# W975.net
KiCad netlist of a schematic drawn in EAGLE
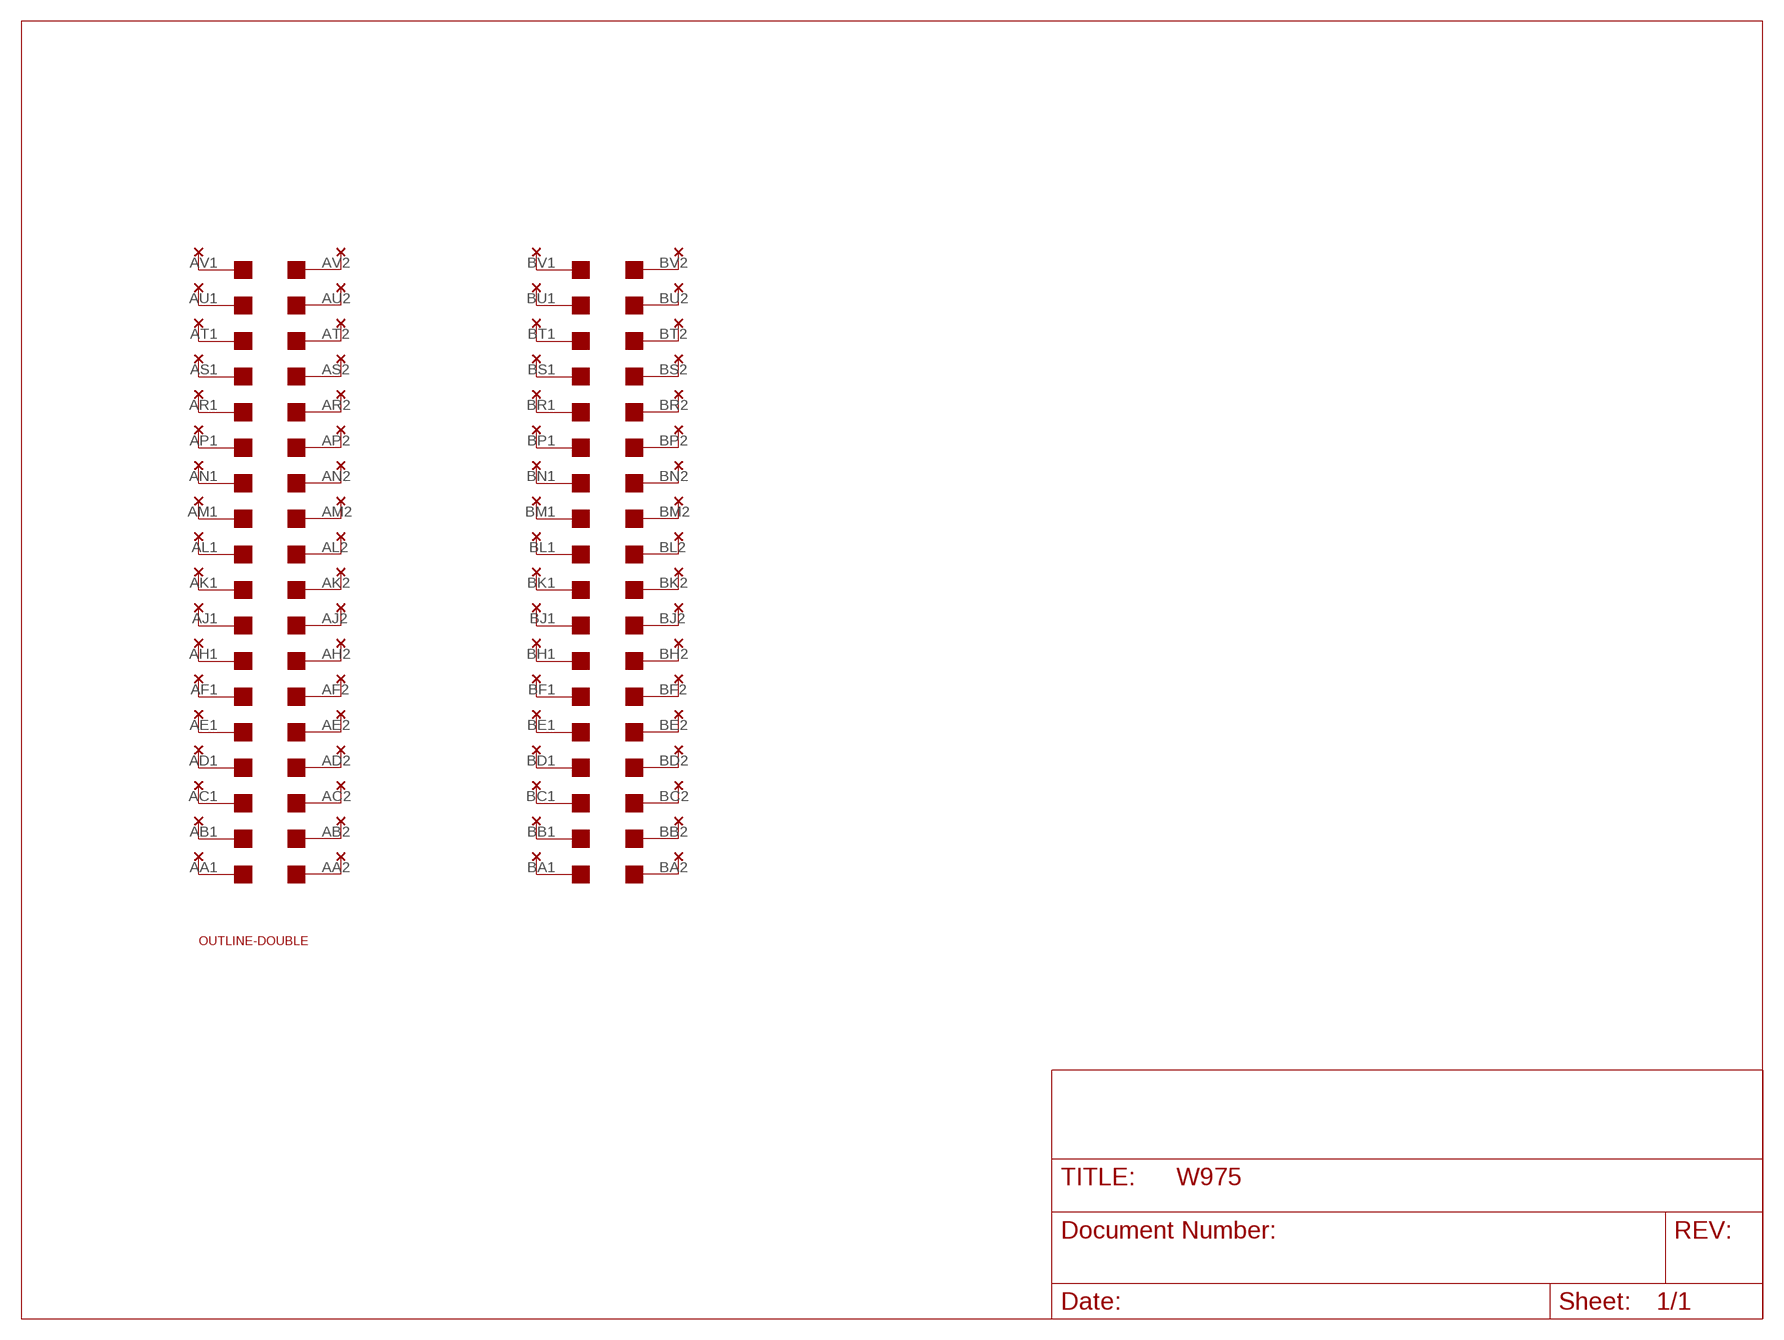
[diagram p0: schematic, sheet 1]

(export (version "E")
  (design (tool "Eeschema 10.0.6"))
  (components
    (comp (ref "A")
      (value "A")
      (footprint "eagle-import:THRU-HOLE2")
      (libsource (lib "eagle-import") (part "THRU-HOLE2W"))
    )
    (comp (ref "B")
      (value "B")
      (footprint "eagle-import:THRU-HOLE2")
      (libsource (lib "eagle-import") (part "THRU-HOLE2W"))
    )
    (comp (ref "U$1")
      (value "OUTLINE-DOUBLE")
      (footprint "eagle-import:DOUBLE")
      (libsource (lib "eagle-import") (part "OUTLINE-DOUBLE"))
    )
    (comp (ref "U$2")
      (value "DOUBLE")
      (footprint "eagle-import:EDGE-CON4")
      (libsource (lib "eagle-import") (part "DOUBLE"))
    )
  )
  (nets
    (net (code "1") (name "Net-(AA-P$1)") (class "Default")
      (node (ref "A") (pin "A1") (pinfunction "P$1_A1") (pintype "passive"))
      (node (ref "U$2") (pin "AA1") (pinfunction "1_AA1") (pintype "bidirectional"))
    )
    (net (code "2") (name "Net-(AAA-P$1)") (class "Default")
      (node (ref "A") (pin "R1") (pinfunction "P$1_R1") (pintype "passive"))
      (node (ref "U$2") (pin "AR1") (pinfunction "1_AR1") (pintype "bidirectional"))
    )
    (net (code "3") (name "Net-(AAB-P$1)") (class "Default")
      (node (ref "A") (pin "R2") (pinfunction "P$1_R2") (pintype "passive"))
      (node (ref "U$2") (pin "AR2") (pinfunction "1_AR2") (pintype "bidirectional"))
    )
    (net (code "4") (name "Net-(AAC-P$1)") (class "Default")
      (node (ref "A") (pin "S1") (pinfunction "P$1_S1") (pintype "passive"))
      (node (ref "U$2") (pin "AS1") (pinfunction "1_AS1") (pintype "bidirectional"))
    )
    (net (code "5") (name "Net-(AAD-P$1)") (class "Default")
      (node (ref "A") (pin "S2") (pinfunction "P$1_S2") (pintype "passive"))
      (node (ref "U$2") (pin "AS2") (pinfunction "1_AS2") (pintype "bidirectional"))
    )
    (net (code "6") (name "Net-(AAE-P$1)") (class "Default")
      (node (ref "A") (pin "T1") (pinfunction "P$1_T1") (pintype "passive"))
      (node (ref "U$2") (pin "AT1") (pinfunction "1_AT1") (pintype "bidirectional"))
    )
    (net (code "7") (name "Net-(AAF-P$1)") (class "Default")
      (node (ref "A") (pin "T2") (pinfunction "P$1_T2") (pintype "passive"))
      (node (ref "U$2") (pin "AT2") (pinfunction "1_AT2") (pintype "bidirectional"))
    )
    (net (code "8") (name "Net-(AAG-P$1)") (class "Default")
      (node (ref "A") (pin "U1") (pinfunction "P$1_U1") (pintype "passive"))
      (node (ref "U$2") (pin "AU1") (pinfunction "1_AU1") (pintype "bidirectional"))
    )
    (net (code "9") (name "Net-(AAH-P$1)") (class "Default")
      (node (ref "A") (pin "U2") (pinfunction "P$1_U2") (pintype "passive"))
      (node (ref "U$2") (pin "AU2") (pinfunction "1_AU2") (pintype "bidirectional"))
    )
    (net (code "10") (name "Net-(AAI-P$1)") (class "Default")
      (node (ref "A") (pin "V1") (pinfunction "P$1_V1") (pintype "passive"))
      (node (ref "U$2") (pin "AV1") (pinfunction "1_AV1") (pintype "bidirectional"))
    )
    (net (code "11") (name "Net-(AAJ-P$1)") (class "Default")
      (node (ref "A") (pin "V2") (pinfunction "P$1_V2") (pintype "passive"))
      (node (ref "U$2") (pin "AV2") (pinfunction "1_AV2") (pintype "bidirectional"))
    )
    (net (code "12") (name "Net-(AB-P$1)") (class "Default")
      (node (ref "A") (pin "A2") (pinfunction "P$1_A2") (pintype "passive"))
      (node (ref "U$2") (pin "AA2") (pinfunction "1_AA2") (pintype "bidirectional"))
    )
    (net (code "13") (name "Net-(AC-P$1)") (class "Default")
      (node (ref "A") (pin "B1") (pinfunction "P$1_B1") (pintype "passive"))
      (node (ref "U$2") (pin "AB1") (pinfunction "1_AB1") (pintype "bidirectional"))
    )
    (net (code "14") (name "Net-(AD-P$1)") (class "Default")
      (node (ref "A") (pin "B2") (pinfunction "P$1_B2") (pintype "passive"))
      (node (ref "U$2") (pin "AB2") (pinfunction "1_AB2") (pintype "bidirectional"))
    )
    (net (code "15") (name "Net-(AE-P$1)") (class "Default")
      (node (ref "A") (pin "C1") (pinfunction "P$1_C1") (pintype "passive"))
      (node (ref "U$2") (pin "AC1") (pinfunction "1_AC1") (pintype "bidirectional"))
    )
    (net (code "16") (name "Net-(AF-P$1)") (class "Default")
      (node (ref "A") (pin "C2") (pinfunction "P$1_C2") (pintype "passive"))
      (node (ref "U$2") (pin "AC2") (pinfunction "1_AC2") (pintype "bidirectional"))
    )
    (net (code "17") (name "Net-(AG-P$1)") (class "Default")
      (node (ref "A") (pin "D1") (pinfunction "P$1_D1") (pintype "passive"))
      (node (ref "U$2") (pin "AD1") (pinfunction "1_AD1") (pintype "bidirectional"))
    )
    (net (code "18") (name "Net-(AH-P$1)") (class "Default")
      (node (ref "A") (pin "D2") (pinfunction "P$1_D2") (pintype "passive"))
      (node (ref "U$2") (pin "AD2") (pinfunction "1_AD2") (pintype "bidirectional"))
    )
    (net (code "19") (name "Net-(AI-P$1)") (class "Default")
      (node (ref "A") (pin "E1") (pinfunction "P$1_E1") (pintype "passive"))
      (node (ref "U$2") (pin "AE1") (pinfunction "1_AE1") (pintype "bidirectional"))
    )
    (net (code "20") (name "Net-(AJ-P$1)") (class "Default")
      (node (ref "A") (pin "E2") (pinfunction "P$1_E2") (pintype "passive"))
      (node (ref "U$2") (pin "AE2") (pinfunction "1_AE2") (pintype "bidirectional"))
    )
    (net (code "21") (name "Net-(AK-P$1)") (class "Default")
      (node (ref "A") (pin "F1") (pinfunction "P$1_F1") (pintype "passive"))
      (node (ref "U$2") (pin "AF1") (pinfunction "1_AF1") (pintype "bidirectional"))
    )
    (net (code "22") (name "Net-(AL-P$1)") (class "Default")
      (node (ref "A") (pin "F2") (pinfunction "P$1_F2") (pintype "passive"))
      (node (ref "U$2") (pin "AF2") (pinfunction "1_AF2") (pintype "bidirectional"))
    )
    (net (code "23") (name "Net-(AM-P$1)") (class "Default")
      (node (ref "A") (pin "H1") (pinfunction "P$1_H1") (pintype "passive"))
      (node (ref "U$2") (pin "AH1") (pinfunction "1_AH1") (pintype "bidirectional"))
    )
    (net (code "24") (name "Net-(AN-P$1)") (class "Default")
      (node (ref "A") (pin "H2") (pinfunction "P$1_H2") (pintype "passive"))
      (node (ref "U$2") (pin "AH2") (pinfunction "1_AH2") (pintype "bidirectional"))
    )
    (net (code "25") (name "Net-(AO-P$1)") (class "Default")
      (node (ref "A") (pin "J1") (pinfunction "P$1_J1") (pintype "passive"))
      (node (ref "U$2") (pin "AJ1") (pinfunction "1_AJ1") (pintype "bidirectional"))
    )
    (net (code "26") (name "Net-(AP-P$1)") (class "Default")
      (node (ref "A") (pin "J2") (pinfunction "P$1_J2") (pintype "passive"))
      (node (ref "U$2") (pin "AJ2") (pinfunction "1_AJ2") (pintype "bidirectional"))
    )
    (net (code "27") (name "Net-(AQ-P$1)") (class "Default")
      (node (ref "A") (pin "K1") (pinfunction "P$1_K1") (pintype "passive"))
      (node (ref "U$2") (pin "AK1") (pinfunction "1_AK1") (pintype "bidirectional"))
    )
    (net (code "28") (name "Net-(AR-P$1)") (class "Default")
      (node (ref "A") (pin "K2") (pinfunction "P$1_K2") (pintype "passive"))
      (node (ref "U$2") (pin "AK2") (pinfunction "1_AK2") (pintype "bidirectional"))
    )
    (net (code "29") (name "Net-(AS-P$1)") (class "Default")
      (node (ref "A") (pin "L1") (pinfunction "P$1_L1") (pintype "passive"))
      (node (ref "U$2") (pin "AL1") (pinfunction "1_AL1") (pintype "bidirectional"))
    )
    (net (code "30") (name "Net-(AT-P$1)") (class "Default")
      (node (ref "A") (pin "L2") (pinfunction "P$1_L2") (pintype "passive"))
      (node (ref "U$2") (pin "AL2") (pinfunction "1_AL2") (pintype "bidirectional"))
    )
    (net (code "31") (name "Net-(AU-P$1)") (class "Default")
      (node (ref "A") (pin "M1") (pinfunction "P$1_M1") (pintype "passive"))
      (node (ref "U$2") (pin "AM1") (pinfunction "1_AM1") (pintype "bidirectional"))
    )
    (net (code "32") (name "Net-(AV-P$1)") (class "Default")
      (node (ref "A") (pin "M2") (pinfunction "P$1_M2") (pintype "passive"))
      (node (ref "U$2") (pin "AM2") (pinfunction "1_AM2") (pintype "bidirectional"))
    )
    (net (code "33") (name "Net-(AW-P$1)") (class "Default")
      (node (ref "A") (pin "N1") (pinfunction "P$1_N1") (pintype "passive"))
      (node (ref "U$2") (pin "AN1") (pinfunction "1_AN1") (pintype "bidirectional"))
    )
    (net (code "34") (name "Net-(AX-P$1)") (class "Default")
      (node (ref "A") (pin "N2") (pinfunction "P$1_N2") (pintype "passive"))
      (node (ref "U$2") (pin "AN2") (pinfunction "1_AN2") (pintype "bidirectional"))
    )
    (net (code "35") (name "Net-(AY-P$1)") (class "Default")
      (node (ref "A") (pin "P1") (pinfunction "P$1_P1") (pintype "passive"))
      (node (ref "U$2") (pin "AP1") (pinfunction "1_AP1") (pintype "bidirectional"))
    )
    (net (code "36") (name "Net-(AZ-P$1)") (class "Default")
      (node (ref "A") (pin "P2") (pinfunction "P$1_P2") (pintype "passive"))
      (node (ref "U$2") (pin "AP2") (pinfunction "1_AP2") (pintype "bidirectional"))
    )
    (net (code "37") (name "Net-(BA-P$1)") (class "Default")
      (node (ref "B") (pin "A1") (pinfunction "P$1_A1") (pintype "passive"))
      (node (ref "U$2") (pin "BA1") (pinfunction "1_BA1") (pintype "bidirectional"))
    )
    (net (code "38") (name "Net-(BAA-P$1)") (class "Default")
      (node (ref "B") (pin "R1") (pinfunction "P$1_R1") (pintype "passive"))
      (node (ref "U$2") (pin "BR1") (pinfunction "1_BR1") (pintype "bidirectional"))
    )
    (net (code "39") (name "Net-(BAB-P$1)") (class "Default")
      (node (ref "B") (pin "R2") (pinfunction "P$1_R2") (pintype "passive"))
      (node (ref "U$2") (pin "BR2") (pinfunction "1_BR2") (pintype "bidirectional"))
    )
    (net (code "40") (name "Net-(BAC-P$1)") (class "Default")
      (node (ref "B") (pin "S1") (pinfunction "P$1_S1") (pintype "passive"))
      (node (ref "U$2") (pin "BS1") (pinfunction "1_BS1") (pintype "bidirectional"))
    )
    (net (code "41") (name "Net-(BAD-P$1)") (class "Default")
      (node (ref "B") (pin "S2") (pinfunction "P$1_S2") (pintype "passive"))
      (node (ref "U$2") (pin "BS2") (pinfunction "1_BS2") (pintype "bidirectional"))
    )
    (net (code "42") (name "Net-(BAE-P$1)") (class "Default")
      (node (ref "B") (pin "T1") (pinfunction "P$1_T1") (pintype "passive"))
      (node (ref "U$2") (pin "BT1") (pinfunction "1_BT1") (pintype "bidirectional"))
    )
    (net (code "43") (name "Net-(BAF-P$1)") (class "Default")
      (node (ref "B") (pin "T2") (pinfunction "P$1_T2") (pintype "passive"))
      (node (ref "U$2") (pin "BT2") (pinfunction "1_BT2") (pintype "bidirectional"))
    )
    (net (code "44") (name "Net-(BAG-P$1)") (class "Default")
      (node (ref "B") (pin "U1") (pinfunction "P$1_U1") (pintype "passive"))
      (node (ref "U$2") (pin "BU1") (pinfunction "1_BU1") (pintype "bidirectional"))
    )
    (net (code "45") (name "Net-(BAH-P$1)") (class "Default")
      (node (ref "B") (pin "U2") (pinfunction "P$1_U2") (pintype "passive"))
      (node (ref "U$2") (pin "BU2") (pinfunction "1_BU2") (pintype "bidirectional"))
    )
    (net (code "46") (name "Net-(BAI-P$1)") (class "Default")
      (node (ref "B") (pin "V1") (pinfunction "P$1_V1") (pintype "passive"))
      (node (ref "U$2") (pin "BV1") (pinfunction "1_BV1") (pintype "bidirectional"))
    )
    (net (code "47") (name "Net-(BAJ-P$1)") (class "Default")
      (node (ref "B") (pin "V2") (pinfunction "P$1_V2") (pintype "passive"))
      (node (ref "U$2") (pin "BV2") (pinfunction "1_BV2") (pintype "bidirectional"))
    )
    (net (code "48") (name "Net-(BB-P$1)") (class "Default")
      (node (ref "B") (pin "A2") (pinfunction "P$1_A2") (pintype "passive"))
      (node (ref "U$2") (pin "BA2") (pinfunction "1_BA2") (pintype "bidirectional"))
    )
    (net (code "49") (name "Net-(BC-P$1)") (class "Default")
      (node (ref "B") (pin "B1") (pinfunction "P$1_B1") (pintype "passive"))
      (node (ref "U$2") (pin "BB1") (pinfunction "1_BB1") (pintype "bidirectional"))
    )
    (net (code "50") (name "Net-(BD-P$1)") (class "Default")
      (node (ref "B") (pin "B2") (pinfunction "P$1_B2") (pintype "passive"))
      (node (ref "U$2") (pin "BB2") (pinfunction "1_BB2") (pintype "bidirectional"))
    )
    (net (code "51") (name "Net-(BE-P$1)") (class "Default")
      (node (ref "B") (pin "C1") (pinfunction "P$1_C1") (pintype "passive"))
      (node (ref "U$2") (pin "BC1") (pinfunction "1_BC1") (pintype "bidirectional"))
    )
    (net (code "52") (name "Net-(BF-P$1)") (class "Default")
      (node (ref "B") (pin "C2") (pinfunction "P$1_C2") (pintype "passive"))
      (node (ref "U$2") (pin "BC2") (pinfunction "1_BC2") (pintype "bidirectional"))
    )
    (net (code "53") (name "Net-(BG-P$1)") (class "Default")
      (node (ref "B") (pin "D1") (pinfunction "P$1_D1") (pintype "passive"))
      (node (ref "U$2") (pin "BD1") (pinfunction "1_BD1") (pintype "bidirectional"))
    )
    (net (code "54") (name "Net-(BH-P$1)") (class "Default")
      (node (ref "B") (pin "D2") (pinfunction "P$1_D2") (pintype "passive"))
      (node (ref "U$2") (pin "BD2") (pinfunction "1_BD2") (pintype "bidirectional"))
    )
    (net (code "55") (name "Net-(BI-P$1)") (class "Default")
      (node (ref "B") (pin "E1") (pinfunction "P$1_E1") (pintype "passive"))
      (node (ref "U$2") (pin "BE1") (pinfunction "1_BE1") (pintype "bidirectional"))
    )
    (net (code "56") (name "Net-(BJ-P$1)") (class "Default")
      (node (ref "B") (pin "E2") (pinfunction "P$1_E2") (pintype "passive"))
      (node (ref "U$2") (pin "BE2") (pinfunction "1_BE2") (pintype "bidirectional"))
    )
    (net (code "57") (name "Net-(BK-P$1)") (class "Default")
      (node (ref "B") (pin "F1") (pinfunction "P$1_F1") (pintype "passive"))
      (node (ref "U$2") (pin "BF1") (pinfunction "1_BF1") (pintype "bidirectional"))
    )
    (net (code "58") (name "Net-(BL-P$1)") (class "Default")
      (node (ref "B") (pin "F2") (pinfunction "P$1_F2") (pintype "passive"))
      (node (ref "U$2") (pin "BF2") (pinfunction "1_BF2") (pintype "bidirectional"))
    )
    (net (code "59") (name "Net-(BM-P$1)") (class "Default")
      (node (ref "B") (pin "H1") (pinfunction "P$1_H1") (pintype "passive"))
      (node (ref "U$2") (pin "BH1") (pinfunction "1_BH1") (pintype "bidirectional"))
    )
    (net (code "60") (name "Net-(BN-P$1)") (class "Default")
      (node (ref "B") (pin "H2") (pinfunction "P$1_H2") (pintype "passive"))
      (node (ref "U$2") (pin "BH2") (pinfunction "1_BH2") (pintype "bidirectional"))
    )
    (net (code "61") (name "Net-(BO-P$1)") (class "Default")
      (node (ref "B") (pin "J1") (pinfunction "P$1_J1") (pintype "passive"))
      (node (ref "U$2") (pin "BJ1") (pinfunction "1_BJ1") (pintype "bidirectional"))
    )
    (net (code "62") (name "Net-(BP-P$1)") (class "Default")
      (node (ref "B") (pin "J2") (pinfunction "P$1_J2") (pintype "passive"))
      (node (ref "U$2") (pin "BJ2") (pinfunction "1_BJ2") (pintype "bidirectional"))
    )
    (net (code "63") (name "Net-(BQ-P$1)") (class "Default")
      (node (ref "B") (pin "K1") (pinfunction "P$1_K1") (pintype "passive"))
      (node (ref "U$2") (pin "BK1") (pinfunction "1_BK1") (pintype "bidirectional"))
    )
    (net (code "64") (name "Net-(BR-P$1)") (class "Default")
      (node (ref "B") (pin "K2") (pinfunction "P$1_K2") (pintype "passive"))
      (node (ref "U$2") (pin "BK2") (pinfunction "1_BK2") (pintype "bidirectional"))
    )
    (net (code "65") (name "Net-(BS-P$1)") (class "Default")
      (node (ref "B") (pin "L1") (pinfunction "P$1_L1") (pintype "passive"))
      (node (ref "U$2") (pin "BL1") (pinfunction "1_BL1") (pintype "bidirectional"))
    )
    (net (code "66") (name "Net-(BT-P$1)") (class "Default")
      (node (ref "B") (pin "L2") (pinfunction "P$1_L2") (pintype "passive"))
      (node (ref "U$2") (pin "BL2") (pinfunction "1_BL2") (pintype "bidirectional"))
    )
    (net (code "67") (name "Net-(BU-P$1)") (class "Default")
      (node (ref "B") (pin "M1") (pinfunction "P$1_M1") (pintype "passive"))
      (node (ref "U$2") (pin "BM1") (pinfunction "1_BM1") (pintype "bidirectional"))
    )
    (net (code "68") (name "Net-(BV-P$1)") (class "Default")
      (node (ref "B") (pin "M2") (pinfunction "P$1_M2") (pintype "passive"))
      (node (ref "U$2") (pin "BM2") (pinfunction "1_BM2") (pintype "bidirectional"))
    )
    (net (code "69") (name "Net-(BW-P$1)") (class "Default")
      (node (ref "B") (pin "N1") (pinfunction "P$1_N1") (pintype "passive"))
      (node (ref "U$2") (pin "BN1") (pinfunction "1_BN1") (pintype "bidirectional"))
    )
    (net (code "70") (name "Net-(BX-P$1)") (class "Default")
      (node (ref "B") (pin "N2") (pinfunction "P$1_N2") (pintype "passive"))
      (node (ref "U$2") (pin "BN2") (pinfunction "1_BN2") (pintype "bidirectional"))
    )
    (net (code "71") (name "Net-(BY-P$1)") (class "Default")
      (node (ref "B") (pin "P1") (pinfunction "P$1_P1") (pintype "passive"))
      (node (ref "U$2") (pin "BP1") (pinfunction "1_BP1") (pintype "bidirectional"))
    )
    (net (code "72") (name "Net-(BZ-P$1)") (class "Default")
      (node (ref "B") (pin "P2") (pinfunction "P$1_P2") (pintype "passive"))
      (node (ref "U$2") (pin "BP2") (pinfunction "1_BP2") (pintype "bidirectional"))
    )
  )
)
